# USB.net
KiCad netlist of a schematic drawn in Altium Designer
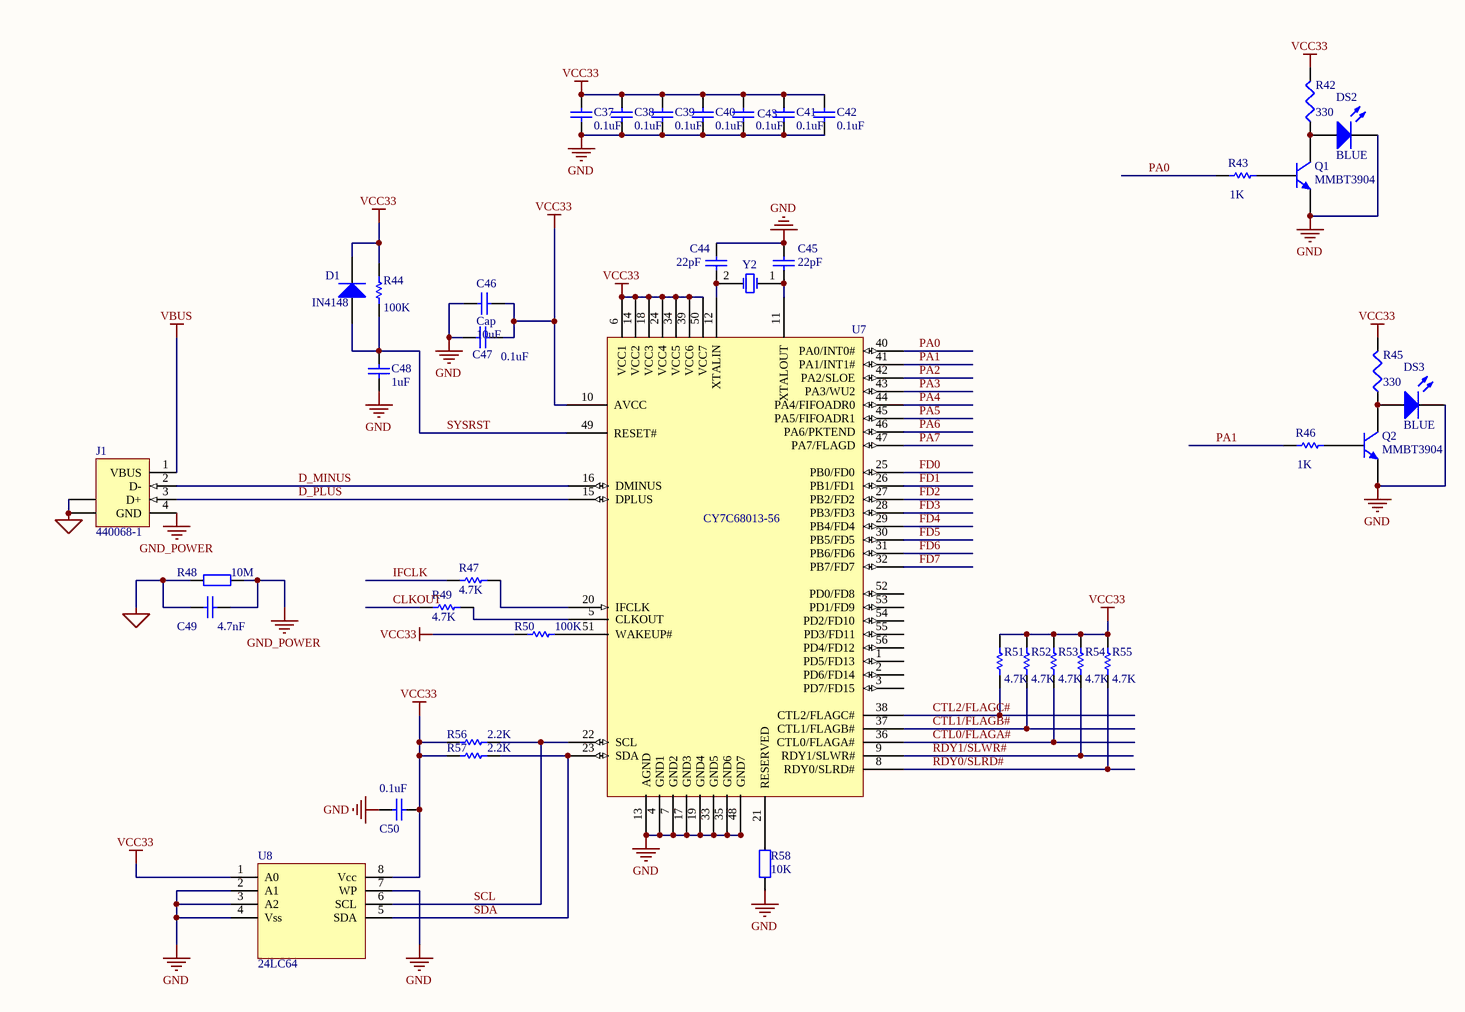
[diagram p0: USB.SchDoc]

(export (version "E")
  (design (tool "Eeschema 10.0.6"))
  (components
    (comp (ref "C37")
      (value "0.1uF")
      (footprint "cc0603")
      (description "Capacitor (Semiconductor SIM Model)")
      (fields (field (name "Comment") "Cap Semi") (field (name "PUBLISHER") "Altium Limited"))
      (libsource (lib "Miscellaneous Devices") (part "Cap Semi"))
    )
    (comp (ref "C38")
      (value "0.1uF")
      (footprint "cc0603")
      (description "Capacitor (Semiconductor SIM Model)")
      (fields (field (name "Comment") "Cap Semi") (field (name "PUBLISHER") "Altium Limited"))
      (libsource (lib "Miscellaneous Devices") (part "Cap Semi"))
    )
    (comp (ref "C39")
      (value "0.1uF")
      (footprint "cc0603")
      (description "Capacitor (Semiconductor SIM Model)")
      (fields (field (name "Comment") "Cap Semi") (field (name "PUBLISHER") "Altium Limited"))
      (libsource (lib "Miscellaneous Devices") (part "Cap Semi"))
    )
    (comp (ref "C40")
      (value "0.1uF")
      (footprint "cc0603")
      (description "Capacitor (Semiconductor SIM Model)")
      (fields (field (name "Comment") "Cap Semi") (field (name "PUBLISHER") "Altium Limited"))
      (libsource (lib "Miscellaneous Devices") (part "Cap Semi"))
    )
    (comp (ref "C41")
      (value "0.1uF")
      (footprint "cc0603")
      (description "Capacitor (Semiconductor SIM Model)")
      (fields (field (name "Comment") "Cap Semi") (field (name "PUBLISHER") "Altium Limited"))
      (libsource (lib "Miscellaneous Devices") (part "Cap Semi"))
    )
    (comp (ref "C42")
      (value "0.1uF")
      (footprint "cc0603")
      (description "Capacitor (Semiconductor SIM Model)")
      (fields (field (name "Comment") "Cap Semi") (field (name "PUBLISHER") "Altium Limited"))
      (libsource (lib "Miscellaneous Devices") (part "Cap Semi"))
    )
    (comp (ref "C43")
      (value "0.1uF")
      (footprint "cc0603")
      (description "Capacitor (Semiconductor SIM Model)")
      (fields (field (name "Comment") "Cap Semi") (field (name "PUBLISHER") "Altium Limited"))
      (libsource (lib "Miscellaneous Devices") (part "Cap Semi"))
    )
    (comp (ref "C44")
      (value "22pF")
      (footprint "cc0603")
      (description "Capacitor (Semiconductor SIM Model)")
      (fields (field (name "Comment") "Cap Semi") (field (name "PUBLISHER") "Altium Limited"))
      (libsource (lib "Miscellaneous Devices") (part "Cap Semi"))
    )
    (comp (ref "C45")
      (value "22pF")
      (footprint "cc0603")
      (description "Capacitor (Semiconductor SIM Model)")
      (fields (field (name "Comment") "Cap Semi") (field (name "PUBLISHER") "Altium Limited"))
      (libsource (lib "Miscellaneous Devices") (part "Cap Semi"))
    )
    (comp (ref "C46")
      (value "Cap")
      (footprint "cc0603")
      (description "Capacitor")
      (fields (field (name "ALTIUM_VALUE") "10uF") (field (name "PUBLISHER") "Altium Limited"))
      (libsource (lib "Miscellaneous Devices") (part "Cap"))
    )
    (comp (ref "C47")
      (value "0.1uF")
      (footprint "cc0603")
      (description "Capacitor (Semiconductor SIM Model)")
      (fields (field (name "Comment") "Cap Semi") (field (name "PUBLISHER") "Altium Limited"))
      (libsource (lib "Miscellaneous Devices") (part "Cap Semi"))
    )
    (comp (ref "C48")
      (value "1uF")
      (footprint "cc0603")
      (description "Capacitor (Semiconductor SIM Model)")
      (fields (field (name "Comment") "Cap Semi") (field (name "PUBLISHER") "Altium Limited"))
      (libsource (lib "Miscellaneous Devices") (part "Cap Semi"))
    )
    (comp (ref "C49")
      (value "4.7nF")
      (footprint "4.7nF")
      (description "Capacitor")
      (fields (field (name "Comment") "Cap") (field (name "PUBLISHER") "Altium Limited"))
      (libsource (lib "Miscellaneous Devices") (part "Cap"))
    )
    (comp (ref "C50")
      (value "0.1uF")
      (footprint "cc0603")
      (description "Capacitor (Semiconductor SIM Model)")
      (fields (field (name "Comment") "Cap Semi") (field (name "PUBLISHER") "Altium Limited"))
      (libsource (lib "Miscellaneous Devices") (part "Cap Semi"))
    )
    (comp (ref "D1")
      (value "IN4148")
      (footprint "myIOBOX:DIODE")
      (description "1 Amp General Purpose Rectifier")
      (fields (field (name "PUBLISHER") "Altium Limited"))
      (libsource (lib "Miscellaneous Devices") (part "Diode 1N4001"))
    )
    (comp (ref "DS2")
      (value "BLUE")
      (footprint "HDR1X2")
      (description "Typical INFRARED GaAs LED")
      (fields (field (name "PUBLISHER") "Altium Limited"))
      (libsource (lib "Miscellaneous Devices") (part "LED0"))
    )
    (comp (ref "DS3")
      (value "BLUE")
      (footprint "HDR1X2")
      (description "Typical INFRARED GaAs LED")
      (fields (field (name "PUBLISHER") "Altium Limited"))
      (libsource (lib "Miscellaneous Devices") (part "LED0"))
    )
    (comp (ref "J1")
      (value "440068-1")
      (footprint "USB_interface_type_B")
      (description "USB 1.1, Right Angle, Thru-Hole, Reverse Type, Receptacle, 4 Position, Black")
      (fields (field (name "PUBLISHER") "Altium Limited"))
      (libsource (lib "AMP Serial Bus USB") (part "440068-1"))
    )
    (comp (ref "Q1")
      (value "MMBT3904")
      (footprint "NPN")
      (description "NPN General Purpose Amplifier")
      (fields (field (name "PUBLISHER") "Altium Limited"))
      (libsource (lib "Miscellaneous Devices") (part "2N3904"))
    )
    (comp (ref "Q2")
      (value "MMBT3904")
      (footprint "NPN")
      (description "NPN General Purpose Amplifier")
      (fields (field (name "PUBLISHER") "Altium Limited"))
      (libsource (lib "Miscellaneous Devices") (part "2N3904"))
    )
    (comp (ref "R42")
      (value "330")
      (footprint "CR0603")
      (description "Resistor")
      (fields (field (name "PUBLISHER") "Altium Limited"))
      (libsource (lib "Miscellaneous Devices") (part "Res3"))
    )
    (comp (ref "R43")
      (value "1K")
      (footprint "CR0603")
      (description "Resistor")
      (fields (field (name "PUBLISHER") "Altium Limited"))
      (libsource (lib "Miscellaneous Devices") (part "Res1"))
    )
    (comp (ref "R44")
      (value "100K")
      (footprint "CR0603")
      (description "Resistor")
      (fields (field (name "Comment") "Res1") (field (name "PUBLISHER") "Altium Limited"))
      (libsource (lib "") (part "Res1_1"))
    )
    (comp (ref "R45")
      (value "330")
      (footprint "CR0603")
      (description "Resistor")
      (fields (field (name "PUBLISHER") "Altium Limited"))
      (libsource (lib "Miscellaneous Devices") (part "Res3"))
    )
    (comp (ref "R46")
      (value "1K")
      (footprint "CR0603")
      (description "Resistor")
      (fields (field (name "PUBLISHER") "Altium Limited"))
      (libsource (lib "Miscellaneous Devices") (part "Res1"))
    )
    (comp (ref "R47")
      (value "4.7K")
      (footprint "CR0603")
      (description "Resistor")
      (fields (field (name "PUBLISHER") "Altium Limited"))
      (libsource (lib "Miscellaneous Devices") (part "Res1"))
    )
    (comp (ref "R48")
      (value "10M")
      (footprint "CR0805")
      (description "Resistor")
      (fields (field (name "Comment") "Res2") (field (name "PUBLISHER") "Altium Limited"))
      (libsource (lib "") (part "Res2_1"))
    )
    (comp (ref "R49")
      (value "4.7K")
      (footprint "CR0603")
      (description "Resistor")
      (fields (field (name "PUBLISHER") "Altium Limited"))
      (libsource (lib "Miscellaneous Devices") (part "Res1"))
    )
    (comp (ref "R50")
      (value "100K")
      (footprint "CR0603")
      (description "Resistor")
      (fields (field (name "Comment") "Res1") (field (name "PUBLISHER") "Altium Limited"))
      (libsource (lib "") (part "Res1_1"))
    )
    (comp (ref "R51")
      (value "4.7K")
      (footprint "CR0603")
      (description "Resistor")
      (fields (field (name "PUBLISHER") "Altium Limited"))
      (libsource (lib "Miscellaneous Devices") (part "Res1"))
    )
    (comp (ref "R52")
      (value "4.7K")
      (footprint "CR0603")
      (description "Resistor")
      (fields (field (name "PUBLISHER") "Altium Limited"))
      (libsource (lib "Miscellaneous Devices") (part "Res1"))
    )
    (comp (ref "R53")
      (value "4.7K")
      (footprint "CR0603")
      (description "Resistor")
      (fields (field (name "PUBLISHER") "Altium Limited"))
      (libsource (lib "Miscellaneous Devices") (part "Res1"))
    )
    (comp (ref "R54")
      (value "4.7K")
      (footprint "CR0603")
      (description "Resistor")
      (fields (field (name "PUBLISHER") "Altium Limited"))
      (libsource (lib "Miscellaneous Devices") (part "Res1"))
    )
    (comp (ref "R55")
      (value "4.7K")
      (footprint "CR0603")
      (description "Resistor")
      (fields (field (name "PUBLISHER") "Altium Limited"))
      (libsource (lib "Miscellaneous Devices") (part "Res1"))
    )
    (comp (ref "R56")
      (value "2.2K")
      (footprint "CR0603")
      (description "Resistor")
      (fields (field (name "Comment") "Res1") (field (name "PUBLISHER") "Altium Limited"))
      (libsource (lib "") (part "Res1_1"))
    )
    (comp (ref "R57")
      (value "2.2K")
      (footprint "CR0603")
      (description "Resistor")
      (fields (field (name "Comment") "Res1") (field (name "PUBLISHER") "Altium Limited"))
      (libsource (lib "") (part "Res1_1"))
    )
    (comp (ref "R58")
      (value "10K")
      (footprint "CR0603")
      (description "Resistor")
      (fields (field (name "Comment") "Res2") (field (name "PUBLISHER") "Altium Limited"))
      (libsource (lib "Miscellaneous Devices") (part "Res2"))
    )
    (comp (ref "U7")
      (value "CY7C68013-56")
      (footprint "so-56")
      (libsource (lib "FCTECHSCH") (part "CY7C68013-56"))
    )
    (comp (ref "U8")
      (value "24LC64")
      (footprint "myIOBOX:sop8")
      (fields (field (name "PUBLISHER") "Altium Limited"))
      (libsource (lib "Altera EPCS Configuration Device") (part "EPCS1SI8"))
    )
    (comp (ref "Y2")
      (value "XTAL")
      (footprint "myIOBOX:USB_jingzhen 24M")
      (description "Crystal Oscillator")
      (fields (field (name "PUBLISHER") "Altium Limited"))
      (libsource (lib "Miscellaneous Devices") (part "XTAL"))
    )
  )
  (nets
    (net (code "1") (name "/CLKOUT") (class "Default")
      (node (ref "R49") (pin "2") (pinfunction "2_2") (pintype "passive"))
    )
    (net (code "2") (name "/CTL0{slash}FLAGA#") (class "Default")
      (node (ref "R53") (pin "1") (pinfunction "1_1") (pintype "passive"))
      (node (ref "U7") (pin "36") (pinfunction "CTL0/FLAGA#_36") (pintype "passive"))
    )
    (net (code "3") (name "/CTL1{slash}FLAGB#") (class "Default")
      (node (ref "R52") (pin "1") (pinfunction "1_1") (pintype "passive"))
      (node (ref "U7") (pin "37") (pinfunction "CTL1/FLAGB#_37") (pintype "passive"))
    )
    (net (code "4") (name "/CTL2{slash}FLAGC#") (class "Default")
      (node (ref "R51") (pin "1") (pinfunction "1_1") (pintype "passive"))
      (node (ref "U7") (pin "38") (pinfunction "CTL2/FLAGC#_38") (pintype "passive"))
    )
    (net (code "5") (name "/D_MINUS") (class "Default")
      (node (ref "J1") (pin "2") (pinfunction "D-_2") (pintype "input"))
      (node (ref "U7") (pin "16") (pinfunction "DMINUS_16") (pintype "bidirectional"))
    )
    (net (code "6") (name "/D_PLUS") (class "Default")
      (node (ref "J1") (pin "3") (pinfunction "D+_3") (pintype "input"))
      (node (ref "U7") (pin "15") (pinfunction "DPLUS_15") (pintype "bidirectional"))
    )
    (net (code "7") (name "/FD0") (class "Default")
      (node (ref "U7") (pin "25") (pinfunction "PB0/FD0_25") (pintype "bidirectional"))
    )
    (net (code "8") (name "/FD1") (class "Default")
      (node (ref "U7") (pin "26") (pinfunction "PB1/FD1_26") (pintype "bidirectional"))
    )
    (net (code "9") (name "/FD2") (class "Default")
      (node (ref "U7") (pin "27") (pinfunction "PB2/FD2_27") (pintype "bidirectional"))
    )
    (net (code "10") (name "/FD3") (class "Default")
      (node (ref "U7") (pin "28") (pinfunction "PB3/FD3_28") (pintype "bidirectional"))
    )
    (net (code "11") (name "/FD4") (class "Default")
      (node (ref "U7") (pin "29") (pinfunction "PB4/FD4_29") (pintype "bidirectional"))
    )
    (net (code "12") (name "/FD5") (class "Default")
      (node (ref "U7") (pin "30") (pinfunction "PB5/FD5_30") (pintype "bidirectional"))
    )
    (net (code "13") (name "/FD6") (class "Default")
      (node (ref "U7") (pin "31") (pinfunction "PB6/FD6_31") (pintype "bidirectional"))
    )
    (net (code "14") (name "/FD7") (class "Default")
      (node (ref "U7") (pin "32") (pinfunction "PB7/FD7_32") (pintype "bidirectional"))
    )
    (net (code "15") (name "/IFCLK") (class "Default")
      (node (ref "R47") (pin "2") (pinfunction "2_2") (pintype "passive"))
    )
    (net (code "16") (name "/PA0") (class "Default")
      (node (ref "R43") (pin "1") (pinfunction "1_1") (pintype "passive"))
      (node (ref "U7") (pin "40") (pinfunction "PA0/INT0#_40") (pintype "bidirectional"))
    )
    (net (code "17") (name "/PA1") (class "Default")
      (node (ref "R46") (pin "1") (pinfunction "1_1") (pintype "passive"))
      (node (ref "U7") (pin "41") (pinfunction "PA1/INT1#_41") (pintype "bidirectional"))
    )
    (net (code "18") (name "/PA2") (class "Default")
      (node (ref "U7") (pin "42") (pinfunction "PA2/SLOE_42") (pintype "bidirectional"))
    )
    (net (code "19") (name "/PA3") (class "Default")
      (node (ref "U7") (pin "43") (pinfunction "PA3/WU2_43") (pintype "bidirectional"))
    )
    (net (code "20") (name "/PA4") (class "Default")
      (node (ref "U7") (pin "44") (pinfunction "PA4/FIFOADR0_44") (pintype "bidirectional"))
    )
    (net (code "21") (name "/PA5") (class "Default")
      (node (ref "U7") (pin "45") (pinfunction "PA5/FIFOADR1_45") (pintype "bidirectional"))
    )
    (net (code "22") (name "/PA6") (class "Default")
      (node (ref "U7") (pin "46") (pinfunction "PA6/PKTEND_46") (pintype "bidirectional"))
    )
    (net (code "23") (name "/PA7") (class "Default")
      (node (ref "U7") (pin "47") (pinfunction "PA7/FLAGD_47") (pintype "bidirectional"))
    )
    (net (code "24") (name "/RDY0{slash}SLRD#") (class "Default")
      (node (ref "R55") (pin "1") (pinfunction "1_1") (pintype "passive"))
      (node (ref "U7") (pin "8") (pinfunction "RDY0/SLRD#_8") (pintype "passive"))
    )
    (net (code "25") (name "/RDY1{slash}SLWR#") (class "Default")
      (node (ref "R54") (pin "1") (pinfunction "1_1") (pintype "passive"))
      (node (ref "U7") (pin "9") (pinfunction "RDY1/SLWR#_9") (pintype "passive"))
    )
    (net (code "26") (name "/SCL") (class "Default")
      (node (ref "R56") (pin "2") (pinfunction "2_2") (pintype "passive"))
      (node (ref "U7") (pin "22") (pinfunction "SCL_22") (pintype "bidirectional"))
      (node (ref "U8") (pin "6") (pinfunction "SCL_6") (pintype "passive"))
    )
    (net (code "27") (name "/SDA") (class "Default")
      (node (ref "R57") (pin "2") (pinfunction "2_2") (pintype "passive"))
      (node (ref "U7") (pin "23") (pinfunction "SDA_23") (pintype "bidirectional"))
      (node (ref "U8") (pin "5") (pinfunction "SDA_5") (pintype "passive"))
    )
    (net (code "28") (name "/SYSRST") (class "Default")
      (node (ref "C48") (pin "2") (pinfunction "2_2") (pintype "passive"))
      (node (ref "D1") (pin "1") (pinfunction "A_1") (pintype "passive"))
      (node (ref "R44") (pin "1") (pinfunction "1_1") (pintype "passive"))
      (node (ref "U7") (pin "49") (pinfunction "RESET#_49") (pintype "passive"))
    )
    (net (code "29") (name "GND") (class "Default")
      (node (ref "C37") (pin "1") (pinfunction "1_1") (pintype "passive"))
      (node (ref "C38") (pin "1") (pinfunction "1_1") (pintype "passive"))
      (node (ref "C39") (pin "1") (pinfunction "1_1") (pintype "passive"))
      (node (ref "C40") (pin "1") (pinfunction "1_1") (pintype "passive"))
      (node (ref "C41") (pin "1") (pinfunction "1_1") (pintype "passive"))
      (node (ref "C42") (pin "1") (pinfunction "1_1") (pintype "passive"))
      (node (ref "C43") (pin "1") (pinfunction "1_1") (pintype "passive"))
      (node (ref "C44") (pin "2") (pinfunction "2_2") (pintype "passive"))
      (node (ref "C45") (pin "1") (pinfunction "1_1") (pintype "passive"))
      (node (ref "C46") (pin "1") (pinfunction "1_1") (pintype "passive"))
      (node (ref "C47") (pin "1") (pinfunction "1_1") (pintype "passive"))
      (node (ref "C48") (pin "1") (pinfunction "1_1") (pintype "passive"))
      (node (ref "C50") (pin "1") (pinfunction "1_1") (pintype "passive"))
      (node (ref "DS2") (pin "2") (pinfunction "K_2") (pintype "passive"))
      (node (ref "DS3") (pin "2") (pinfunction "K_2") (pintype "passive"))
      (node (ref "Q1") (pin "1") (pinfunction "E_1") (pintype "passive"))
      (node (ref "Q2") (pin "1") (pinfunction "E_1") (pintype "passive"))
      (node (ref "R58") (pin "1") (pinfunction "1_1") (pintype "passive"))
      (node (ref "U7") (pin "13") (pinfunction "AGND_13") (pintype "power_in"))
      (node (ref "U7") (pin "17") (pinfunction "GND3_17") (pintype "power_in"))
      (node (ref "U7") (pin "19") (pinfunction "GND4_19") (pintype "power_in"))
      (node (ref "U7") (pin "33") (pinfunction "GND5_33") (pintype "power_in"))
      (node (ref "U7") (pin "35") (pinfunction "GND6_35") (pintype "power_in"))
      (node (ref "U7") (pin "4") (pinfunction "GND1_4") (pintype "power_in"))
      (node (ref "U7") (pin "48") (pinfunction "GND7_48") (pintype "passive"))
      (node (ref "U7") (pin "7") (pinfunction "GND2_7") (pintype "power_in"))
      (node (ref "U8") (pin "2") (pinfunction "A1_2") (pintype "passive"))
      (node (ref "U8") (pin "3") (pinfunction "A2_3") (pintype "passive"))
      (node (ref "U8") (pin "4") (pinfunction "Vss_4") (pintype "power_in"))
      (node (ref "U8") (pin "7") (pinfunction "WP_7") (pintype "passive"))
    )
    (net (code "30") (name "GND_POWER") (class "Default")
      (node (ref "C49") (pin "2") (pinfunction "2_2") (pintype "passive"))
      (node (ref "J1") (pin "4") (pinfunction "GND_4") (pintype "power_in"))
      (node (ref "R48") (pin "2") (pinfunction "2_2") (pintype "passive"))
    )
    (net (code "31") (name "Net-(DS2-A)") (class "Default")
      (node (ref "DS2") (pin "1") (pinfunction "A_1") (pintype "passive"))
      (node (ref "Q1") (pin "3") (pinfunction "C_3") (pintype "passive"))
      (node (ref "R42") (pin "1") (pinfunction "1_1") (pintype "passive"))
    )
    (net (code "32") (name "Net-(DS3-A)") (class "Default")
      (node (ref "DS3") (pin "1") (pinfunction "A_1") (pintype "passive"))
      (node (ref "Q2") (pin "3") (pinfunction "C_3") (pintype "passive"))
      (node (ref "R45") (pin "1") (pinfunction "1_1") (pintype "passive"))
    )
    (net (code "33") (name "Net-(Q1-B)") (class "Default")
      (node (ref "Q1") (pin "2") (pinfunction "B_2") (pintype "passive"))
      (node (ref "R43") (pin "2") (pinfunction "2_2") (pintype "passive"))
    )
    (net (code "34") (name "Net-(Q2-B)") (class "Default")
      (node (ref "Q2") (pin "2") (pinfunction "B_2") (pintype "passive"))
      (node (ref "R46") (pin "2") (pinfunction "2_2") (pintype "passive"))
    )
    (net (code "35") (name "Net-(U7-CLKOUT)") (class "Default")
      (node (ref "R49") (pin "1") (pinfunction "1_1") (pintype "passive"))
      (node (ref "U7") (pin "5") (pinfunction "CLKOUT_5") (pintype "passive"))
    )
    (net (code "36") (name "Net-(U7-IFCLK)") (class "Default")
      (node (ref "R47") (pin "1") (pinfunction "1_1") (pintype "passive"))
      (node (ref "U7") (pin "20") (pinfunction "IFCLK_20") (pintype "input"))
    )
    (net (code "37") (name "Net-(U7-RESERVED)") (class "Default")
      (node (ref "R58") (pin "2") (pinfunction "2_2") (pintype "passive"))
      (node (ref "U7") (pin "21") (pinfunction "RESERVED_21") (pintype "passive"))
    )
    (net (code "38") (name "Net-(U7-WAKEUP#)") (class "Default")
      (node (ref "R50") (pin "1") (pinfunction "1_1") (pintype "passive"))
      (node (ref "U7") (pin "51") (pinfunction "WAKEUP#_51") (pintype "passive"))
    )
    (net (code "39") (name "Net-(U7-XTALIN)") (class "Default")
      (node (ref "C44") (pin "1") (pinfunction "1_1") (pintype "passive"))
      (node (ref "U7") (pin "12") (pinfunction "XTALIN_12") (pintype "passive"))
      (node (ref "Y2") (pin "2") (pinfunction "OSC2_2") (pintype "passive"))
    )
    (net (code "40") (name "Net-(U7-XTALOUT)") (class "Default")
      (node (ref "C45") (pin "2") (pinfunction "2_2") (pintype "passive"))
      (node (ref "U7") (pin "11") (pinfunction "XTALOUT_11") (pintype "passive"))
      (node (ref "Y2") (pin "1") (pinfunction "OSC1_1") (pintype "passive"))
    )
    (net (code "41") (name "USBSHEILD") (class "Default")
      (node (ref "C49") (pin "1") (pinfunction "1_1") (pintype "passive"))
      (node (ref "J1") (pin "5") (pinfunction "SHLD_5") (pintype "passive"))
      (node (ref "J1") (pin "6") (pinfunction "SHLD_6") (pintype "passive"))
      (node (ref "R48") (pin "1") (pinfunction "1_1") (pintype "passive"))
    )
    (net (code "42") (name "VBUS") (class "Default")
      (node (ref "J1") (pin "1") (pinfunction "VBUS_1") (pintype "power_in"))
    )
    (net (code "43") (name "VCC33") (class "Default")
      (node (ref "C37") (pin "2") (pinfunction "2_2") (pintype "passive"))
      (node (ref "C38") (pin "2") (pinfunction "2_2") (pintype "passive"))
      (node (ref "C39") (pin "2") (pinfunction "2_2") (pintype "passive"))
      (node (ref "C40") (pin "2") (pinfunction "2_2") (pintype "passive"))
      (node (ref "C41") (pin "2") (pinfunction "2_2") (pintype "passive"))
      (node (ref "C42") (pin "2") (pinfunction "2_2") (pintype "passive"))
      (node (ref "C43") (pin "2") (pinfunction "2_2") (pintype "passive"))
      (node (ref "C46") (pin "2") (pinfunction "2_2") (pintype "passive"))
      (node (ref "C47") (pin "2") (pinfunction "2_2") (pintype "passive"))
      (node (ref "C50") (pin "2") (pinfunction "2_2") (pintype "passive"))
      (node (ref "D1") (pin "2") (pinfunction "K_2") (pintype "passive"))
      (node (ref "R42") (pin "2") (pinfunction "2_2") (pintype "passive"))
      (node (ref "R44") (pin "2") (pinfunction "2_2") (pintype "passive"))
      (node (ref "R45") (pin "2") (pinfunction "2_2") (pintype "passive"))
      (node (ref "R50") (pin "2") (pinfunction "2_2") (pintype "passive"))
      (node (ref "R51") (pin "2") (pinfunction "2_2") (pintype "passive"))
      (node (ref "R52") (pin "2") (pinfunction "2_2") (pintype "passive"))
      (node (ref "R53") (pin "2") (pinfunction "2_2") (pintype "passive"))
      (node (ref "R54") (pin "2") (pinfunction "2_2") (pintype "passive"))
      (node (ref "R55") (pin "2") (pinfunction "2_2") (pintype "passive"))
      (node (ref "R56") (pin "1") (pinfunction "1_1") (pintype "passive"))
      (node (ref "R57") (pin "1") (pinfunction "1_1") (pintype "passive"))
      (node (ref "U7") (pin "10") (pinfunction "AVCC_10") (pintype "power_in"))
      (node (ref "U7") (pin "14") (pinfunction "VCC2_14") (pintype "passive"))
      (node (ref "U7") (pin "18") (pinfunction "VCC3_18") (pintype "passive"))
      (node (ref "U7") (pin "24") (pinfunction "VCC4_24") (pintype "passive"))
      (node (ref "U7") (pin "34") (pinfunction "VCC5_34") (pintype "passive"))
      (node (ref "U7") (pin "39") (pinfunction "VCC6_39") (pintype "passive"))
      (node (ref "U7") (pin "50") (pinfunction "VCC7_50") (pintype "passive"))
      (node (ref "U7") (pin "6") (pinfunction "VCC1_6") (pintype "passive"))
      (node (ref "U8") (pin "1") (pinfunction "A0_1") (pintype "passive"))
      (node (ref "U8") (pin "8") (pinfunction "Vcc_8") (pintype "power_in"))
    )
    (net (code "44") (name "unconnected-(U7-PD0{slash}FD8-Pad52)") (class "Default")
      (node (ref "U7") (pin "52") (pinfunction "PD0/FD8_52") (pintype "bidirectional"))
    )
    (net (code "45") (name "unconnected-(U7-PD1{slash}FD9-Pad53)") (class "Default")
      (node (ref "U7") (pin "53") (pinfunction "PD1/FD9_53") (pintype "bidirectional"))
    )
    (net (code "46") (name "unconnected-(U7-PD2{slash}FD10-Pad54)") (class "Default")
      (node (ref "U7") (pin "54") (pinfunction "PD2/FD10_54") (pintype "bidirectional"))
    )
    (net (code "47") (name "unconnected-(U7-PD3{slash}FD11-Pad55)") (class "Default")
      (node (ref "U7") (pin "55") (pinfunction "PD3/FD11_55") (pintype "bidirectional"))
    )
    (net (code "48") (name "unconnected-(U7-PD4{slash}FD12-Pad56)") (class "Default")
      (node (ref "U7") (pin "56") (pinfunction "PD4/FD12_56") (pintype "bidirectional"))
    )
    (net (code "49") (name "unconnected-(U7-PD5{slash}FD13-Pad1)") (class "Default")
      (node (ref "U7") (pin "1") (pinfunction "PD5/FD13_1") (pintype "bidirectional"))
    )
    (net (code "50") (name "unconnected-(U7-PD6{slash}FD14-Pad2)") (class "Default")
      (node (ref "U7") (pin "2") (pinfunction "PD6/FD14_2") (pintype "bidirectional"))
    )
    (net (code "51") (name "unconnected-(U7-PD7{slash}FD15-Pad3)") (class "Default")
      (node (ref "U7") (pin "3") (pinfunction "PD7/FD15_3") (pintype "bidirectional"))
    )
  )
)
